# Kicking_Device_v13b.net
KiCad netlist of a schematic drawn in EAGLE
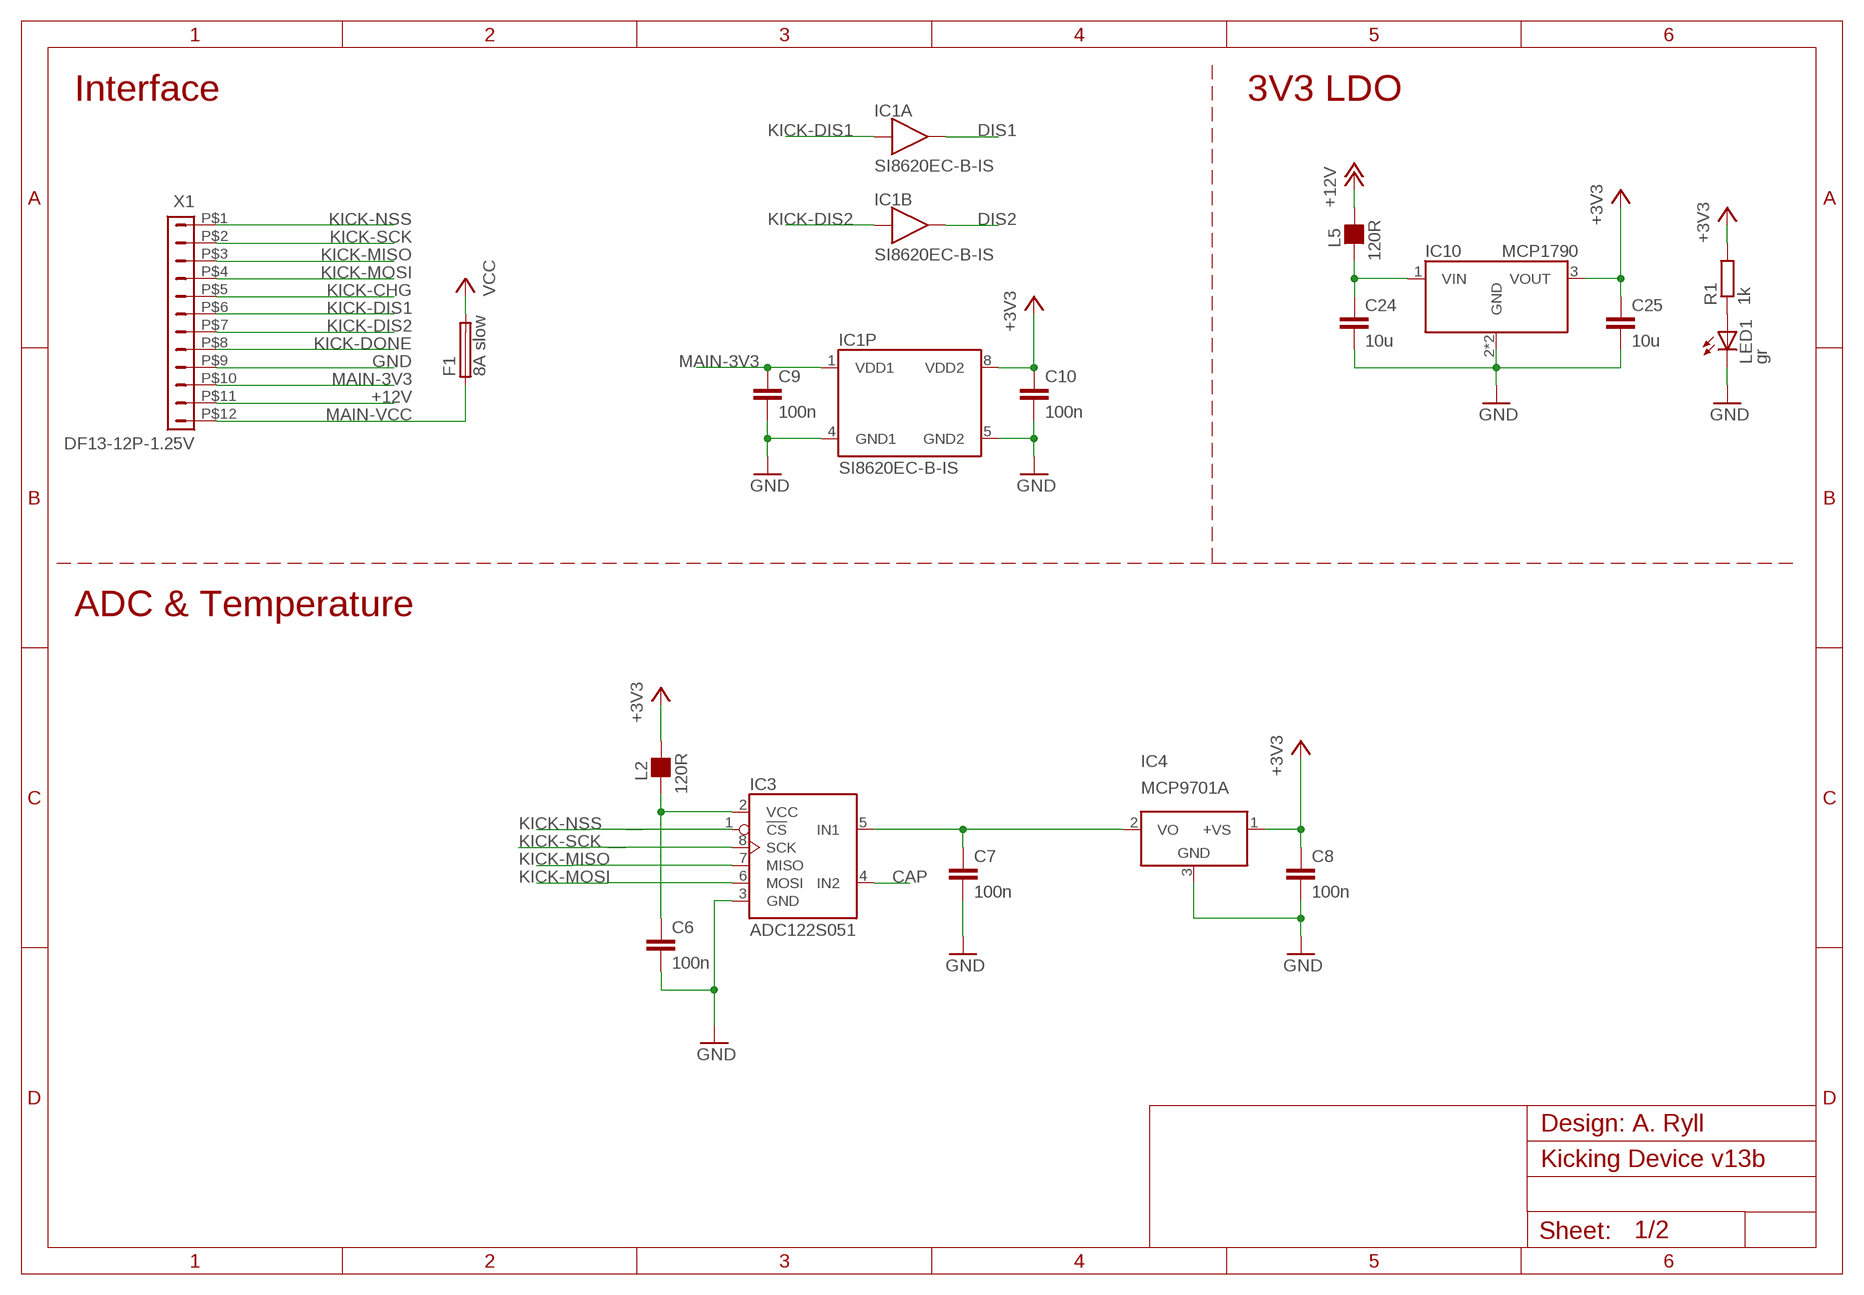
[diagram p0: schematic, sheet 1]
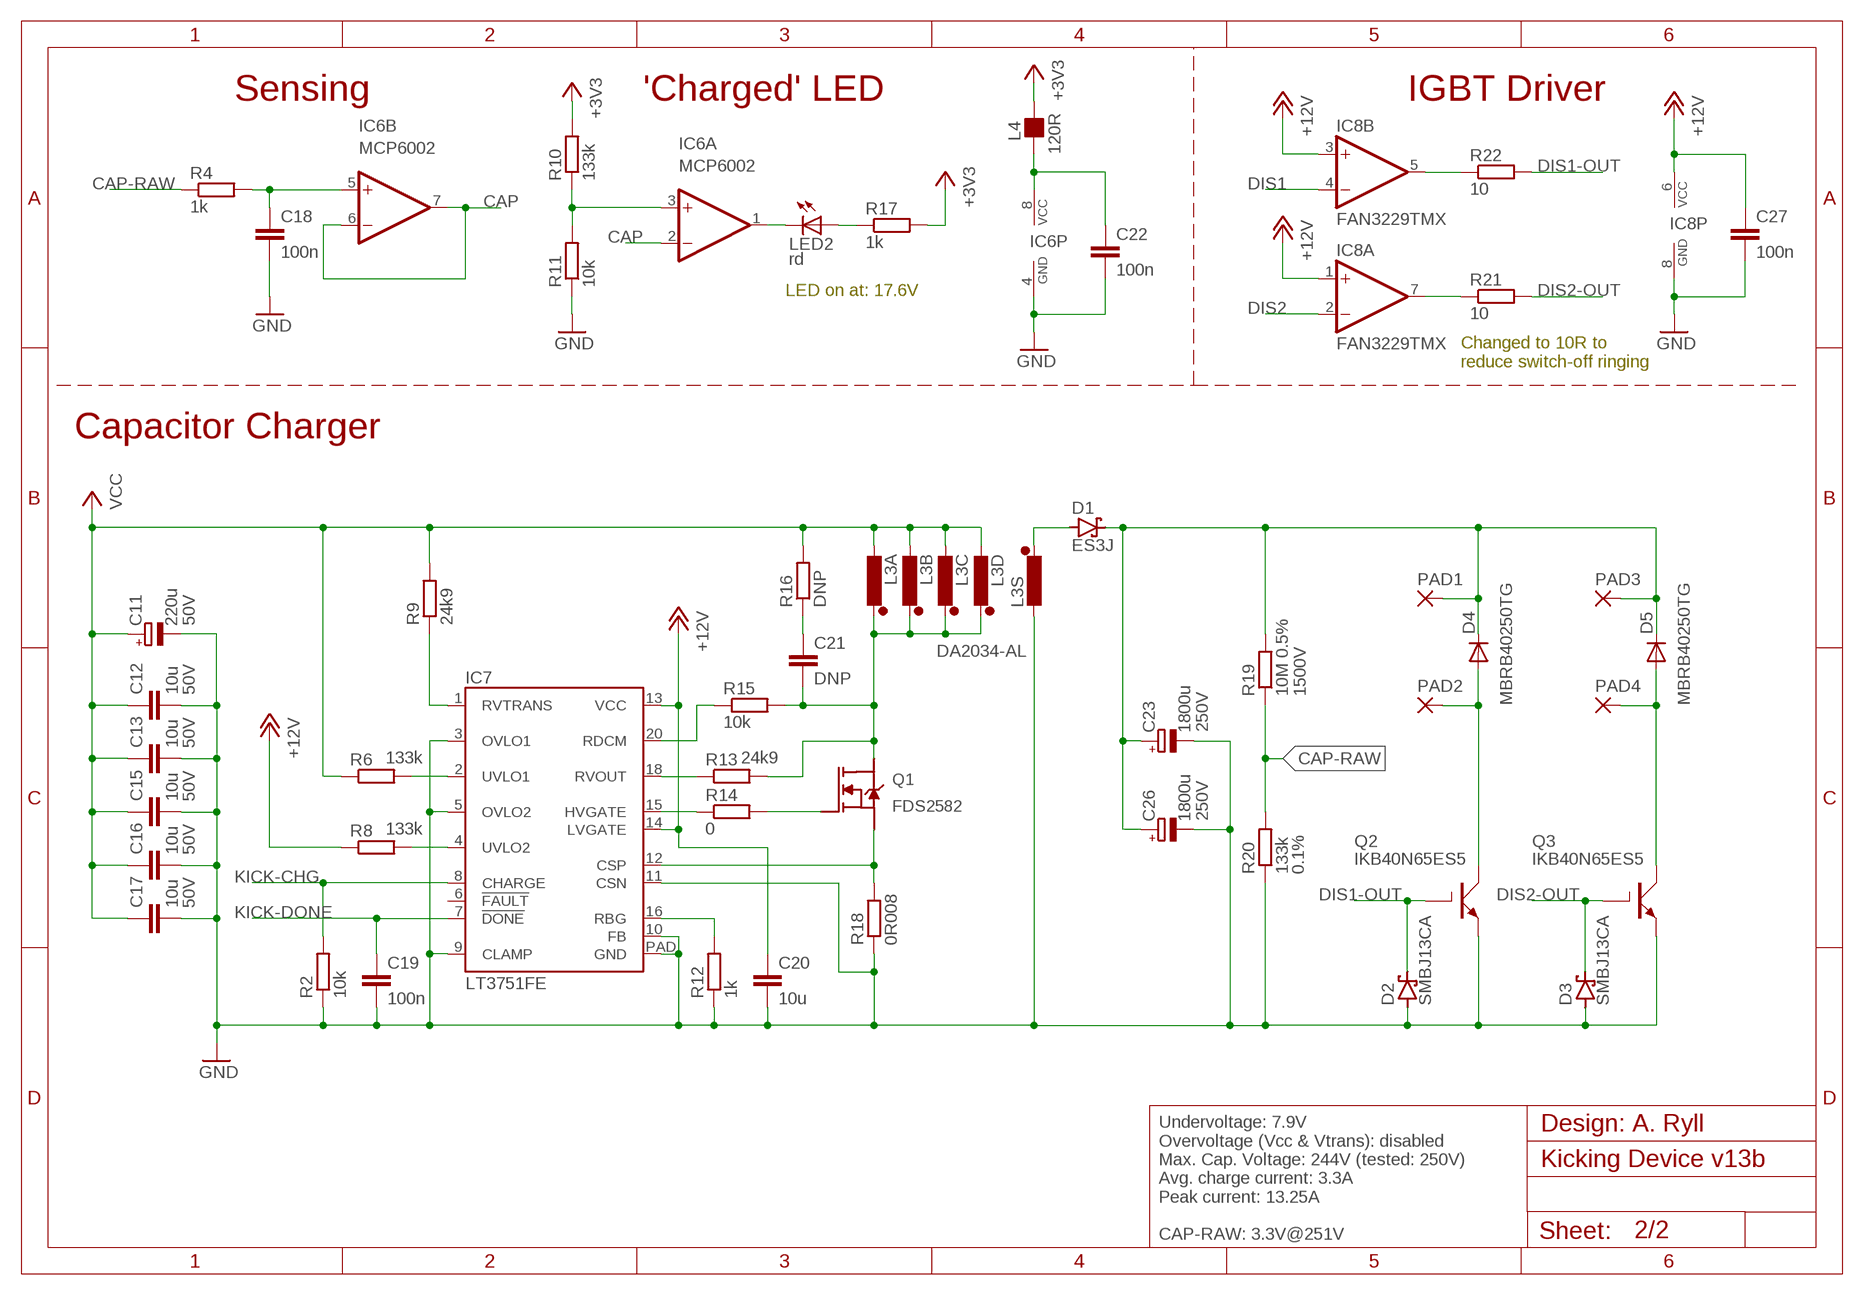
[diagram p1: schematic, sheet 2]

(export (version "E")
  (design (tool "Eeschema 10.0.6"))
  (components
    (comp (ref "C11")
      (value "220u")
      (footprint "eagle-import:PANASONIC_F")
      (fields (field (name "VMAX") "50V"))
      (libsource (lib "eagle-import") (part "CPOL-EUF"))
    )
    (comp (ref "C12")
      (value "10u")
      (footprint "eagle-import:C1210")
      (fields (field (name "VMAX") "50V"))
      (libsource (lib "eagle-import") (part "C-EUC1210"))
    )
    (comp (ref "C13")
      (value "10u")
      (footprint "eagle-import:C1210")
      (fields (field (name "VMAX") "50V"))
      (libsource (lib "eagle-import") (part "C-EUC1210"))
    )
    (comp (ref "C15")
      (value "10u")
      (footprint "eagle-import:C1210")
      (fields (field (name "VMAX") "50V"))
      (libsource (lib "eagle-import") (part "C-EUC1210"))
    )
    (comp (ref "C16")
      (value "10u")
      (footprint "eagle-import:C1210")
      (fields (field (name "VMAX") "50V"))
      (libsource (lib "eagle-import") (part "C-EUC1210"))
    )
    (comp (ref "C17")
      (value "10u")
      (footprint "eagle-import:C1210")
      (fields (field (name "VMAX") "50V"))
      (libsource (lib "eagle-import") (part "C-EUC1210"))
    )
    (comp (ref "C18")
      (value "100n")
      (footprint "eagle-import:C0603")
      (libsource (lib "eagle-import") (part "C-EUC0603"))
    )
    (comp (ref "C19")
      (value "100n")
      (footprint "eagle-import:C0603")
      (libsource (lib "eagle-import") (part "C-EUC0603"))
    )
    (comp (ref "C20")
      (value "10u")
      (footprint "eagle-import:C0603")
      (libsource (lib "eagle-import") (part "C-EUC0603"))
    )
    (comp (ref "C21")
      (value "DNP")
      (footprint "eagle-import:C0805")
      (libsource (lib "eagle-import") (part "C-EUC0805"))
    )
    (comp (ref "C22")
      (value "100n")
      (footprint "eagle-import:C0603")
      (libsource (lib "eagle-import") (part "C-EUC0603"))
    )
    (comp (ref "C23")
      (value "1800u")
      (footprint "eagle-import:EB35D")
      (fields (field (name "VMAX") "250V"))
      (libsource (lib "eagle-import") (part "CPOL-EUE10-35"))
    )
    (comp (ref "C26")
      (value "1800u")
      (footprint "eagle-import:EB35D")
      (fields (field (name "VMAX") "250V"))
      (libsource (lib "eagle-import") (part "CPOL-EUE10-35"))
    )
    (comp (ref "C27")
      (value "100n")
      (footprint "eagle-import:C0603")
      (libsource (lib "eagle-import") (part "C-EUC0603"))
    )
    (comp (ref "D1")
      (value "ES3J")
      (footprint "eagle-import:SMC")
      (libsource (lib "eagle-import") (part "SCHOTTKY-DIODESMC"))
    )
    (comp (ref "D2")
      (value "SMBJ13CA")
      (footprint "eagle-import:SMB")
      (libsource (lib "eagle-import") (part "SCHOTTKY-DIODESMD"))
    )
    (comp (ref "D3")
      (value "SMBJ13CA")
      (footprint "eagle-import:SMB")
      (libsource (lib "eagle-import") (part "SCHOTTKY-DIODESMD"))
    )
    (comp (ref "D4")
      (value "MBRB40250TG")
      (footprint "eagle-import:D2PAK")
      (libsource (lib "eagle-import") (part "DIODED2"))
    )
    (comp (ref "D5")
      (value "MBRB40250TG")
      (footprint "eagle-import:D2PAK")
      (libsource (lib "eagle-import") (part "DIODED2"))
    )
    (comp (ref "IC6")
      (value "MCP6002")
      (footprint "eagle-import:SOIC8N")
      (libsource (lib "eagle-import") (part "AD-OP2SN"))
    )
    (comp (ref "IC7")
      (value "LT3751FE")
      (footprint "eagle-import:TSSOP20P")
      (libsource (lib "eagle-import") (part "LT3751FE"))
    )
    (comp (ref "IC8")
      (value "FAN3229TMX")
      (footprint "eagle-import:SOIC8N")
      (libsource (lib "eagle-import") (part "FAN3229_MXN"))
    )
    (comp (ref "L3")
      (value "DA2034-AL")
      (footprint "eagle-import:DA2034-AL")
      (libsource (lib "eagle-import") (part "DA203X-AL4"))
    )
    (comp (ref "L4")
      (value "120R")
      (footprint "eagle-import:L0603")
      (libsource (lib "eagle-import") (part "FB_0603"))
    )
    (comp (ref "LED2")
      (value "rd")
      (footprint "eagle-import:CHIP-LED0603")
      (libsource (lib "eagle-import") (part "LEDCHIP-LED0603"))
    )
    (comp (ref "PAD1")
      (value "WIREPAD2,54/1,0")
      (footprint "eagle-import:2,54_1,0")
      (libsource (lib "eagle-import") (part "WIREPAD2,54/1,0"))
    )
    (comp (ref "PAD2")
      (value "WIREPAD2,54/1,0")
      (footprint "eagle-import:2,54_1,0")
      (libsource (lib "eagle-import") (part "WIREPAD2,54/1,0"))
    )
    (comp (ref "PAD3")
      (value "WIREPAD2,54/1,0")
      (footprint "eagle-import:2,54_1,0")
      (libsource (lib "eagle-import") (part "WIREPAD2,54/1,0"))
    )
    (comp (ref "PAD4")
      (value "WIREPAD2,54/1,0")
      (footprint "eagle-import:2,54_1,0")
      (libsource (lib "eagle-import") (part "WIREPAD2,54/1,0"))
    )
    (comp (ref "Q1")
      (value "FDS2582")
      (footprint "eagle-import:SOIC8N")
      (libsource (lib "eagle-import") (part "NMOSSOIC8N"))
    )
    (comp (ref "Q2")
      (value "IKB40N65ES5")
      (footprint "eagle-import:D2PAK")
      (libsource (lib "eagle-import") (part "IGBTTO263AB"))
    )
    (comp (ref "Q3")
      (value "IKB40N65ES5")
      (footprint "eagle-import:D2PAK")
      (libsource (lib "eagle-import") (part "IGBTTO263AB"))
    )
    (comp (ref "R2")
      (value "10k")
      (footprint "eagle-import:R0603")
      (libsource (lib "eagle-import") (part "R-EU_R0603"))
    )
    (comp (ref "R4")
      (value "1k")
      (footprint "eagle-import:R0603")
      (libsource (lib "eagle-import") (part "R-EU_R0603"))
    )
    (comp (ref "R6")
      (value "133k")
      (footprint "eagle-import:R0603")
      (libsource (lib "eagle-import") (part "R-EU_R0603"))
    )
    (comp (ref "R8")
      (value "133k")
      (footprint "eagle-import:R0603")
      (libsource (lib "eagle-import") (part "R-EU_R0603"))
    )
    (comp (ref "R9")
      (value "24k9")
      (footprint "eagle-import:R0603")
      (libsource (lib "eagle-import") (part "R-EU_R0603"))
    )
    (comp (ref "R10")
      (value "133k")
      (footprint "eagle-import:R0603")
      (libsource (lib "eagle-import") (part "R-EU_R0603"))
    )
    (comp (ref "R11")
      (value "10k")
      (footprint "eagle-import:R0603")
      (libsource (lib "eagle-import") (part "R-EU_R0603"))
    )
    (comp (ref "R12")
      (value "1k")
      (footprint "eagle-import:R0603")
      (libsource (lib "eagle-import") (part "R-EU_R0603"))
    )
    (comp (ref "R13")
      (value "24k9")
      (footprint "eagle-import:R0603")
      (libsource (lib "eagle-import") (part "R-EU_R0603"))
    )
    (comp (ref "R14")
      (value "0")
      (footprint "eagle-import:R1206")
      (libsource (lib "eagle-import") (part "R-EU_R1206"))
    )
    (comp (ref "R15")
      (value "10k")
      (footprint "eagle-import:R0603")
      (libsource (lib "eagle-import") (part "R-EU_R0603"))
    )
    (comp (ref "R16")
      (value "DNP")
      (footprint "eagle-import:R0805")
      (libsource (lib "eagle-import") (part "R-EU_R0805"))
    )
    (comp (ref "R17")
      (value "1k")
      (footprint "eagle-import:R0603")
      (libsource (lib "eagle-import") (part "R-EU_R0603"))
    )
    (comp (ref "R18")
      (value "0R008")
      (footprint "eagle-import:R1206")
      (libsource (lib "eagle-import") (part "R-EU_R1206"))
    )
    (comp (ref "R19")
      (value "10M 0.5%")
      (footprint "eagle-import:R1206")
      (fields (field (name "VMAX") "1500V"))
      (libsource (lib "eagle-import") (part "R-EU_R1206"))
    )
    (comp (ref "R20")
      (value "133k")
      (footprint "eagle-import:R0603")
      (fields (field (name "TOL") "0.1%"))
      (libsource (lib "eagle-import") (part "R-EU_R0603"))
    )
    (comp (ref "R21")
      (value "10")
      (footprint "eagle-import:R1206")
      (libsource (lib "eagle-import") (part "R-EU_R1206"))
    )
    (comp (ref "R22")
      (value "10")
      (footprint "eagle-import:R1206")
      (libsource (lib "eagle-import") (part "R-EU_R1206"))
    )
    (comp (ref "C6")
      (value "100n")
      (footprint "eagle-import:C0603")
      (libsource (lib "eagle-import") (part "C-EUC0603"))
    )
    (comp (ref "C7")
      (value "100n")
      (footprint "eagle-import:C0603")
      (libsource (lib "eagle-import") (part "C-EUC0603"))
    )
    (comp (ref "C8")
      (value "100n")
      (footprint "eagle-import:C0603")
      (libsource (lib "eagle-import") (part "C-EUC0603"))
    )
    (comp (ref "C9")
      (value "100n")
      (footprint "eagle-import:C0603")
      (libsource (lib "eagle-import") (part "C-EUC0603"))
    )
    (comp (ref "C10")
      (value "100n")
      (footprint "eagle-import:C0603")
      (libsource (lib "eagle-import") (part "C-EUC0603"))
    )
    (comp (ref "C24")
      (value "10u")
      (footprint "eagle-import:C0603")
      (libsource (lib "eagle-import") (part "C-EUC0603"))
    )
    (comp (ref "C25")
      (value "10u")
      (footprint "eagle-import:C0603")
      (libsource (lib "eagle-import") (part "C-EUC0603"))
    )
    (comp (ref "F1")
      (value "8A slow")
      (footprint "eagle-import:1206")
      (libsource (lib "eagle-import") (part "FUSES"))
    )
    (comp (ref "IC1")
      (value "SI8620EC-B-IS")
      (footprint "eagle-import:SOIC8N")
      (libsource (lib "eagle-import") (part "SI8620"))
    )
    (comp (ref "IC3")
      (value "ADC122S051")
      (footprint "eagle-import:MSOP8")
      (libsource (lib "eagle-import") (part "ADC__2S__1"))
    )
    (comp (ref "IC4")
      (value "MCP9701A")
      (footprint "eagle-import:SOT23")
      (libsource (lib "eagle-import") (part "LM60S"))
    )
    (comp (ref "IC10")
      (value "MCP1790")
      (footprint "eagle-import:SOT223")
      (libsource (lib "eagle-import") (part "MCP1790"))
    )
    (comp (ref "L2")
      (value "120R")
      (footprint "eagle-import:L0603")
      (libsource (lib "eagle-import") (part "FB_0603"))
    )
    (comp (ref "L5")
      (value "120R")
      (footprint "eagle-import:L0603")
      (libsource (lib "eagle-import") (part "FB_0603"))
    )
    (comp (ref "LED1")
      (value "gr")
      (footprint "eagle-import:CHIP-LED0603")
      (libsource (lib "eagle-import") (part "LEDCHIP-LED0603"))
    )
    (comp (ref "R1")
      (value "1k")
      (footprint "eagle-import:R0603")
      (libsource (lib "eagle-import") (part "R-EU_R0603"))
    )
    (comp (ref "X1")
      (value "DF13-12P-1.25V")
      (footprint "eagle-import:DF13C-12P-1.25V")
      (libsource (lib "eagle-import") (part "DF13-12P-1.25V"))
    )
  )
  (nets
    (net (code "1") (name "+3V3") (class "Default")
      (node (ref "C10") (pin "1") (pinfunction "1_1") (pintype "passive"))
      (node (ref "C25") (pin "1") (pinfunction "1_1") (pintype "passive"))
      (node (ref "C8") (pin "1") (pinfunction "1_1") (pintype "passive"))
      (node (ref "IC1") (pin "8") (pinfunction "VDD2_8") (pintype "passive"))
      (node (ref "IC10") (pin "3") (pinfunction "VOUT_3") (pintype "bidirectional"))
      (node (ref "IC4") (pin "1") (pinfunction "+VS_1") (pintype "input"))
      (node (ref "L2") (pin "2") (pinfunction "2_2") (pintype "passive"))
      (node (ref "L4") (pin "2") (pinfunction "2_2") (pintype "passive"))
      (node (ref "R1") (pin "2") (pinfunction "2_2") (pintype "passive"))
      (node (ref "R10") (pin "2") (pinfunction "2_2") (pintype "passive"))
      (node (ref "R17") (pin "2") (pinfunction "2_2") (pintype "passive"))
    )
    (net (code "2") (name "+12V") (class "Default")
      (node (ref "C20") (pin "1") (pinfunction "1_1") (pintype "passive"))
      (node (ref "C27") (pin "1") (pinfunction "1_1") (pintype "passive"))
      (node (ref "IC7") (pin "13") (pinfunction "VCC_13") (pintype "bidirectional"))
      (node (ref "IC7") (pin "14") (pinfunction "LVGATE_14") (pintype "bidirectional"))
      (node (ref "IC8") (pin "1") (pinfunction "+IN_1") (pintype "input"))
      (node (ref "IC8") (pin "3") (pinfunction "+IN_3") (pintype "input"))
      (node (ref "IC8") (pin "6") (pinfunction "VCC_6") (pintype "power_in"))
      (node (ref "L5") (pin "2") (pinfunction "2_2") (pintype "passive"))
      (node (ref "R8") (pin "1") (pinfunction "1_1") (pintype "passive"))
      (node (ref "X1") (pin "P$11") (pinfunction "11_P$11") (pintype "passive"))
    )
    (net (code "3") (name "CAP") (class "Default")
      (node (ref "IC3") (pin "4") (pinfunction "IN2_4") (pintype "passive"))
      (node (ref "IC6") (pin "2") (pinfunction "-IN_2") (pintype "input"))
      (node (ref "IC6") (pin "6") (pinfunction "-IN_6") (pintype "input"))
      (node (ref "IC6") (pin "7") (pinfunction "OUT_7") (pintype "output"))
    )
    (net (code "4") (name "CAP-RAW") (class "Default")
      (node (ref "R19") (pin "1") (pinfunction "1_1") (pintype "passive"))
      (node (ref "R20") (pin "2") (pinfunction "2_2") (pintype "passive"))
      (node (ref "R4") (pin "1") (pinfunction "1_1") (pintype "passive"))
    )
    (net (code "5") (name "DIS1") (class "Default")
      (node (ref "IC1") (pin "7") (pinfunction "OUT_7") (pintype "output"))
      (node (ref "IC8") (pin "4") (pinfunction "-IN_4") (pintype "input"))
    )
    (net (code "6") (name "DIS1-OUT") (class "Default")
      (node (ref "D2") (pin "C") (pinfunction "C_C") (pintype "passive"))
      (node (ref "Q2") (pin "1") (pinfunction "G_1") (pintype "passive"))
      (node (ref "R22") (pin "2") (pinfunction "2_2") (pintype "passive"))
    )
    (net (code "7") (name "DIS2") (class "Default")
      (node (ref "IC1") (pin "6") (pinfunction "OUT_6") (pintype "output"))
      (node (ref "IC8") (pin "2") (pinfunction "-IN_2") (pintype "input"))
    )
    (net (code "8") (name "DIS2-OUT") (class "Default")
      (node (ref "D3") (pin "C") (pinfunction "C_C") (pintype "passive"))
      (node (ref "Q3") (pin "1") (pinfunction "G_1") (pintype "passive"))
      (node (ref "R21") (pin "2") (pinfunction "2_2") (pintype "passive"))
    )
    (net (code "9") (name "GND") (class "Default")
      (node (ref "C10") (pin "2") (pinfunction "2_2") (pintype "passive"))
      (node (ref "C11") (pin "-") (pinfunction "-_-") (pintype "passive"))
      (node (ref "C12") (pin "2") (pinfunction "2_2") (pintype "passive"))
      (node (ref "C13") (pin "2") (pinfunction "2_2") (pintype "passive"))
      (node (ref "C15") (pin "2") (pinfunction "2_2") (pintype "passive"))
      (node (ref "C16") (pin "2") (pinfunction "2_2") (pintype "passive"))
      (node (ref "C17") (pin "2") (pinfunction "2_2") (pintype "passive"))
      (node (ref "C18") (pin "2") (pinfunction "2_2") (pintype "passive"))
      (node (ref "C19") (pin "2") (pinfunction "2_2") (pintype "passive"))
      (node (ref "C20") (pin "2") (pinfunction "2_2") (pintype "passive"))
      (node (ref "C22") (pin "2") (pinfunction "2_2") (pintype "passive"))
      (node (ref "C23") (pin "-") (pinfunction "-_-") (pintype "passive"))
      (node (ref "C24") (pin "2") (pinfunction "2_2") (pintype "passive"))
      (node (ref "C25") (pin "2") (pinfunction "2_2") (pintype "passive"))
      (node (ref "C26") (pin "-") (pinfunction "-_-") (pintype "passive"))
      (node (ref "C27") (pin "2") (pinfunction "2_2") (pintype "passive"))
      (node (ref "C6") (pin "2") (pinfunction "2_2") (pintype "passive"))
      (node (ref "C7") (pin "2") (pinfunction "2_2") (pintype "passive"))
      (node (ref "C8") (pin "2") (pinfunction "2_2") (pintype "passive"))
      (node (ref "C9") (pin "2") (pinfunction "2_2") (pintype "passive"))
      (node (ref "D2") (pin "A") (pinfunction "A_A") (pintype "passive"))
      (node (ref "D3") (pin "A") (pinfunction "A_A") (pintype "passive"))
      (node (ref "IC1") (pin "4") (pinfunction "GND1_4") (pintype "passive"))
      (node (ref "IC1") (pin "5") (pinfunction "GND2_5") (pintype "passive"))
      (node (ref "IC10") (pin "2") (pinfunction "GND_2") (pintype "bidirectional"))
      (node (ref "IC10") (pin "4") (pinfunction "GND_4") (pintype "bidirectional"))
      (node (ref "IC3") (pin "3") (pinfunction "GND_3") (pintype "power_in"))
      (node (ref "IC4") (pin "3") (pinfunction "GND_3") (pintype "power_in"))
      (node (ref "IC6") (pin "4") (pinfunction "GND_4") (pintype "power_in"))
      (node (ref "IC7") (pin "10") (pinfunction "FB_10") (pintype "bidirectional"))
      (node (ref "IC7") (pin "11") (pinfunction "CSN_11") (pintype "bidirectional"))
      (node (ref "IC7") (pin "3") (pinfunction "OVLO1_3") (pintype "bidirectional"))
      (node (ref "IC7") (pin "5") (pinfunction "OVLO2_5") (pintype "bidirectional"))
      (node (ref "IC7") (pin "9") (pinfunction "CLAMP_9") (pintype "bidirectional"))
      (node (ref "IC7") (pin "PAD") (pinfunction "GND_PAD") (pintype "bidirectional"))
      (node (ref "IC8") (pin "8") (pinfunction "GND_8") (pintype "power_in"))
      (node (ref "L3") (pin "12") (pinfunction "2_12") (pintype "passive"))
      (node (ref "LED1") (pin "C") (pinfunction "C_C") (pintype "passive"))
      (node (ref "Q2") (pin "3") (pinfunction "E_3") (pintype "passive"))
      (node (ref "Q3") (pin "3") (pinfunction "E_3") (pintype "passive"))
      (node (ref "R11") (pin "1") (pinfunction "1_1") (pintype "passive"))
      (node (ref "R12") (pin "1") (pinfunction "1_1") (pintype "passive"))
      (node (ref "R18") (pin "1") (pinfunction "1_1") (pintype "passive"))
      (node (ref "R2") (pin "1") (pinfunction "1_1") (pintype "passive"))
      (node (ref "R20") (pin "1") (pinfunction "1_1") (pintype "passive"))
      (node (ref "X1") (pin "P$9") (pinfunction "9_P$9") (pintype "passive"))
    )
    (net (code "10") (name "KICK-CHG") (class "Default")
      (node (ref "IC7") (pin "8") (pinfunction "CHARGE_8") (pintype "bidirectional"))
      (node (ref "R2") (pin "2") (pinfunction "2_2") (pintype "passive"))
      (node (ref "X1") (pin "P$5") (pinfunction "5_P$5") (pintype "passive"))
    )
    (net (code "11") (name "KICK-DIS1") (class "Default")
      (node (ref "IC1") (pin "2") (pinfunction "IN_2") (pintype "input"))
      (node (ref "X1") (pin "P$6") (pinfunction "6_P$6") (pintype "passive"))
    )
    (net (code "12") (name "KICK-DIS2") (class "Default")
      (node (ref "IC1") (pin "3") (pinfunction "IN_3") (pintype "input"))
      (node (ref "X1") (pin "P$7") (pinfunction "7_P$7") (pintype "passive"))
    )
    (net (code "13") (name "KICK-DONE") (class "Default")
      (node (ref "C19") (pin "1") (pinfunction "1_1") (pintype "passive"))
      (node (ref "IC7") (pin "7") (pinfunction "~{DONE}_7") (pintype "bidirectional"))
      (node (ref "X1") (pin "P$8") (pinfunction "8_P$8") (pintype "passive"))
    )
    (net (code "14") (name "KICK-MISO") (class "Default")
      (node (ref "IC3") (pin "7") (pinfunction "MISO_7") (pintype "bidirectional"))
      (node (ref "X1") (pin "P$3") (pinfunction "3_P$3") (pintype "passive"))
    )
    (net (code "15") (name "KICK-MOSI") (class "Default")
      (node (ref "IC3") (pin "6") (pinfunction "MOSI_6") (pintype "bidirectional"))
      (node (ref "X1") (pin "P$4") (pinfunction "4_P$4") (pintype "passive"))
    )
    (net (code "16") (name "KICK-NSS") (class "Default")
      (node (ref "IC3") (pin "1") (pinfunction "~{CS}_1") (pintype "bidirectional"))
      (node (ref "X1") (pin "P$1") (pinfunction "1_P$1") (pintype "passive"))
    )
    (net (code "17") (name "KICK-SCK") (class "Default")
      (node (ref "IC3") (pin "8") (pinfunction "SCK_8") (pintype "bidirectional"))
      (node (ref "X1") (pin "P$2") (pinfunction "2_P$2") (pintype "passive"))
    )
    (net (code "18") (name "MAIN-3V3") (class "Default")
      (node (ref "C9") (pin "1") (pinfunction "1_1") (pintype "passive"))
      (node (ref "IC1") (pin "1") (pinfunction "VDD1_1") (pintype "passive"))
      (node (ref "X1") (pin "P$10") (pinfunction "10_P$10") (pintype "passive"))
    )
    (net (code "19") (name "MAIN-VCC") (class "Default")
      (node (ref "F1") (pin "1") (pinfunction "1_1") (pintype "passive"))
      (node (ref "X1") (pin "P$12") (pinfunction "12_P$12") (pintype "passive"))
    )
    (net (code "20") (name "Net-(C21-Pad1)") (class "Default")
      (node (ref "C21") (pin "1") (pinfunction "1_1") (pintype "passive"))
      (node (ref "R16") (pin "1") (pinfunction "1_1") (pintype "passive"))
    )
    (net (code "21") (name "Net-(D1-PadA)") (class "Default")
      (node (ref "D1") (pin "A") (pinfunction "A_A") (pintype "passive"))
      (node (ref "L3") (pin "1") (pinfunction "1_1") (pintype "passive"))
    )
    (net (code "22") (name "Net-(D4-C)") (class "Default")
      (node (ref "C23") (pin "+") (pinfunction "+_+") (pintype "passive"))
      (node (ref "C26") (pin "+") (pinfunction "+_+") (pintype "passive"))
      (node (ref "D1") (pin "C") (pinfunction "C_C") (pintype "passive"))
      (node (ref "D4") (pin "2") (pinfunction "C_2") (pintype "passive"))
      (node (ref "D5") (pin "2") (pinfunction "C_2") (pintype "passive"))
      (node (ref "PAD1") (pin "1") (pinfunction "P_1") (pintype "passive"))
      (node (ref "PAD3") (pin "1") (pinfunction "P_1") (pintype "passive"))
      (node (ref "R19") (pin "2") (pinfunction "2_2") (pintype "passive"))
    )
    (net (code "23") (name "Net-(IC3-IN1)") (class "Default")
      (node (ref "C7") (pin "1") (pinfunction "1_1") (pintype "passive"))
      (node (ref "IC3") (pin "5") (pinfunction "IN1_5") (pintype "passive"))
      (node (ref "IC4") (pin "2") (pinfunction "VO_2") (pintype "input"))
    )
    (net (code "24") (name "Net-(IC3-VCC)") (class "Default")
      (node (ref "C6") (pin "1") (pinfunction "1_1") (pintype "passive"))
      (node (ref "IC3") (pin "2") (pinfunction "VCC_2") (pintype "power_in"))
      (node (ref "L2") (pin "1") (pinfunction "1_1") (pintype "passive"))
    )
    (net (code "25") (name "Net-(IC6A-+IN)") (class "Default")
      (node (ref "IC6") (pin "3") (pinfunction "+IN_3") (pintype "input"))
      (node (ref "R10") (pin "1") (pinfunction "1_1") (pintype "passive"))
      (node (ref "R11") (pin "2") (pinfunction "2_2") (pintype "passive"))
    )
    (net (code "26") (name "Net-(IC6A-OUT)") (class "Default")
      (node (ref "IC6") (pin "1") (pinfunction "OUT_1") (pintype "output"))
      (node (ref "LED2") (pin "C") (pinfunction "C_C") (pintype "passive"))
    )
    (net (code "27") (name "Net-(IC6B-+IN)") (class "Default")
      (node (ref "C18") (pin "1") (pinfunction "1_1") (pintype "passive"))
      (node (ref "IC6") (pin "5") (pinfunction "+IN_5") (pintype "input"))
      (node (ref "R4") (pin "2") (pinfunction "2_2") (pintype "passive"))
    )
    (net (code "28") (name "Net-(IC6C-VCC)") (class "Default")
      (node (ref "C22") (pin "1") (pinfunction "1_1") (pintype "passive"))
      (node (ref "IC6") (pin "8") (pinfunction "VCC_8") (pintype "power_in"))
      (node (ref "L4") (pin "1") (pinfunction "1_1") (pintype "passive"))
    )
    (net (code "29") (name "Net-(IC7-CSP)") (class "Default")
      (node (ref "IC7") (pin "12") (pinfunction "CSP_12") (pintype "bidirectional"))
      (node (ref "Q1") (pin "1") (pinfunction "S_1") (pintype "passive"))
      (node (ref "Q1") (pin "2") (pinfunction "S_2") (pintype "passive"))
      (node (ref "Q1") (pin "3") (pinfunction "S_3") (pintype "passive"))
      (node (ref "R18") (pin "2") (pinfunction "2_2") (pintype "passive"))
    )
    (net (code "30") (name "Net-(IC7-HVGATE)") (class "Default")
      (node (ref "IC7") (pin "15") (pinfunction "HVGATE_15") (pintype "bidirectional"))
      (node (ref "R14") (pin "1") (pinfunction "1_1") (pintype "passive"))
    )
    (net (code "31") (name "Net-(IC7-RBG)") (class "Default")
      (node (ref "IC7") (pin "16") (pinfunction "RBG_16") (pintype "bidirectional"))
      (node (ref "R12") (pin "2") (pinfunction "2_2") (pintype "passive"))
    )
    (net (code "32") (name "Net-(IC7-RDCM)") (class "Default")
      (node (ref "IC7") (pin "20") (pinfunction "RDCM_20") (pintype "bidirectional"))
      (node (ref "R15") (pin "1") (pinfunction "1_1") (pintype "passive"))
    )
    (net (code "33") (name "Net-(IC7-RVOUT)") (class "Default")
      (node (ref "IC7") (pin "18") (pinfunction "RVOUT_18") (pintype "bidirectional"))
      (node (ref "R13") (pin "1") (pinfunction "1_1") (pintype "passive"))
    )
    (net (code "34") (name "Net-(IC7-RVTRANS)") (class "Default")
      (node (ref "IC7") (pin "1") (pinfunction "RVTRANS_1") (pintype "bidirectional"))
      (node (ref "R9") (pin "1") (pinfunction "1_1") (pintype "passive"))
    )
    (net (code "35") (name "Net-(IC7-UVLO1)") (class "Default")
      (node (ref "IC7") (pin "2") (pinfunction "UVLO1_2") (pintype "bidirectional"))
      (node (ref "R6") (pin "2") (pinfunction "2_2") (pintype "passive"))
    )
    (net (code "36") (name "Net-(IC7-UVLO2)") (class "Default")
      (node (ref "IC7") (pin "4") (pinfunction "UVLO2_4") (pintype "bidirectional"))
      (node (ref "R8") (pin "2") (pinfunction "2_2") (pintype "passive"))
    )
    (net (code "37") (name "Net-(IC8A-OUT)") (class "Default")
      (node (ref "IC8") (pin "7") (pinfunction "OUT_7") (pintype "output"))
      (node (ref "R21") (pin "1") (pinfunction "1_1") (pintype "passive"))
    )
    (net (code "38") (name "Net-(IC8B-OUT)") (class "Default")
      (node (ref "IC8") (pin "5") (pinfunction "OUT_5") (pintype "output"))
      (node (ref "R22") (pin "1") (pinfunction "1_1") (pintype "passive"))
    )
    (net (code "39") (name "Net-(IC10-VIN)") (class "Default")
      (node (ref "C24") (pin "1") (pinfunction "1_1") (pintype "passive"))
      (node (ref "IC10") (pin "1") (pinfunction "VIN_1") (pintype "bidirectional"))
      (node (ref "L5") (pin "1") (pinfunction "1_1") (pintype "passive"))
    )
    (net (code "40") (name "Net-(L3A-1)") (class "Default")
      (node (ref "C21") (pin "2") (pinfunction "2_2") (pintype "passive"))
      (node (ref "L3") (pin "10") (pinfunction "1_10") (pintype "passive"))
      (node (ref "L3") (pin "7") (pinfunction "1_7") (pintype "passive"))
      (node (ref "L3") (pin "8") (pinfunction "1_8") (pintype "passive"))
      (node (ref "L3") (pin "9") (pinfunction "1_9") (pintype "passive"))
      (node (ref "Q1") (pin "5") (pinfunction "D_5") (pintype "passive"))
      (node (ref "Q1") (pin "6") (pinfunction "D_6") (pintype "passive"))
      (node (ref "Q1") (pin "7") (pinfunction "D_7") (pintype "passive"))
      (node (ref "Q1") (pin "8") (pinfunction "D_8") (pintype "passive"))
      (node (ref "R13") (pin "2") (pinfunction "2_2") (pintype "passive"))
      (node (ref "R15") (pin "2") (pinfunction "2_2") (pintype "passive"))
    )
    (net (code "41") (name "Net-(LED1-PadA)") (class "Default")
      (node (ref "LED1") (pin "A") (pinfunction "A_A") (pintype "passive"))
      (node (ref "R1") (pin "1") (pinfunction "1_1") (pintype "passive"))
    )
    (net (code "42") (name "Net-(LED2-PadA)") (class "Default")
      (node (ref "LED2") (pin "A") (pinfunction "A_A") (pintype "passive"))
      (node (ref "R17") (pin "1") (pinfunction "1_1") (pintype "passive"))
    )
    (net (code "43") (name "Net-(PAD2-P)") (class "Default")
      (node (ref "D4") (pin "1") (pinfunction "A_1") (pintype "passive"))
      (node (ref "D4") (pin "3") (pinfunction "A_3") (pintype "passive"))
      (node (ref "PAD2") (pin "1") (pinfunction "P_1") (pintype "passive"))
      (node (ref "Q2") (pin "2") (pinfunction "C_2") (pintype "passive"))
    )
    (net (code "44") (name "Net-(PAD4-P)") (class "Default")
      (node (ref "D5") (pin "1") (pinfunction "A_1") (pintype "passive"))
      (node (ref "D5") (pin "3") (pinfunction "A_3") (pintype "passive"))
      (node (ref "PAD4") (pin "1") (pinfunction "P_1") (pintype "passive"))
      (node (ref "Q3") (pin "2") (pinfunction "C_2") (pintype "passive"))
    )
    (net (code "45") (name "Net-(Q1-G)") (class "Default")
      (node (ref "Q1") (pin "4") (pinfunction "G_4") (pintype "passive"))
      (node (ref "R14") (pin "2") (pinfunction "2_2") (pintype "passive"))
    )
    (net (code "46") (name "VCC") (class "Default")
      (node (ref "C11") (pin "+") (pinfunction "+_+") (pintype "passive"))
      (node (ref "C12") (pin "1") (pinfunction "1_1") (pintype "passive"))
      (node (ref "C13") (pin "1") (pinfunction "1_1") (pintype "passive"))
      (node (ref "C15") (pin "1") (pinfunction "1_1") (pintype "passive"))
      (node (ref "C16") (pin "1") (pinfunction "1_1") (pintype "passive"))
      (node (ref "C17") (pin "1") (pinfunction "1_1") (pintype "passive"))
      (node (ref "F1") (pin "2") (pinfunction "2_2") (pintype "passive"))
      (node (ref "L3") (pin "3") (pinfunction "2_3") (pintype "passive"))
      (node (ref "L3") (pin "4") (pinfunction "2_4") (pintype "passive"))
      (node (ref "L3") (pin "5") (pinfunction "2_5") (pintype "passive"))
      (node (ref "L3") (pin "6") (pinfunction "2_6") (pintype "passive"))
      (node (ref "R16") (pin "2") (pinfunction "2_2") (pintype "passive"))
      (node (ref "R6") (pin "1") (pinfunction "1_1") (pintype "passive"))
      (node (ref "R9") (pin "2") (pinfunction "2_2") (pintype "passive"))
    )
    (net (code "47") (name "unconnected-(IC7-~{FAULT}-Pad6)") (class "Default")
      (node (ref "IC7") (pin "6") (pinfunction "~{FAULT}_6") (pintype "bidirectional"))
    )
  )
)
